# v110.net
KiCad netlist of a schematic drawn in EAGLE
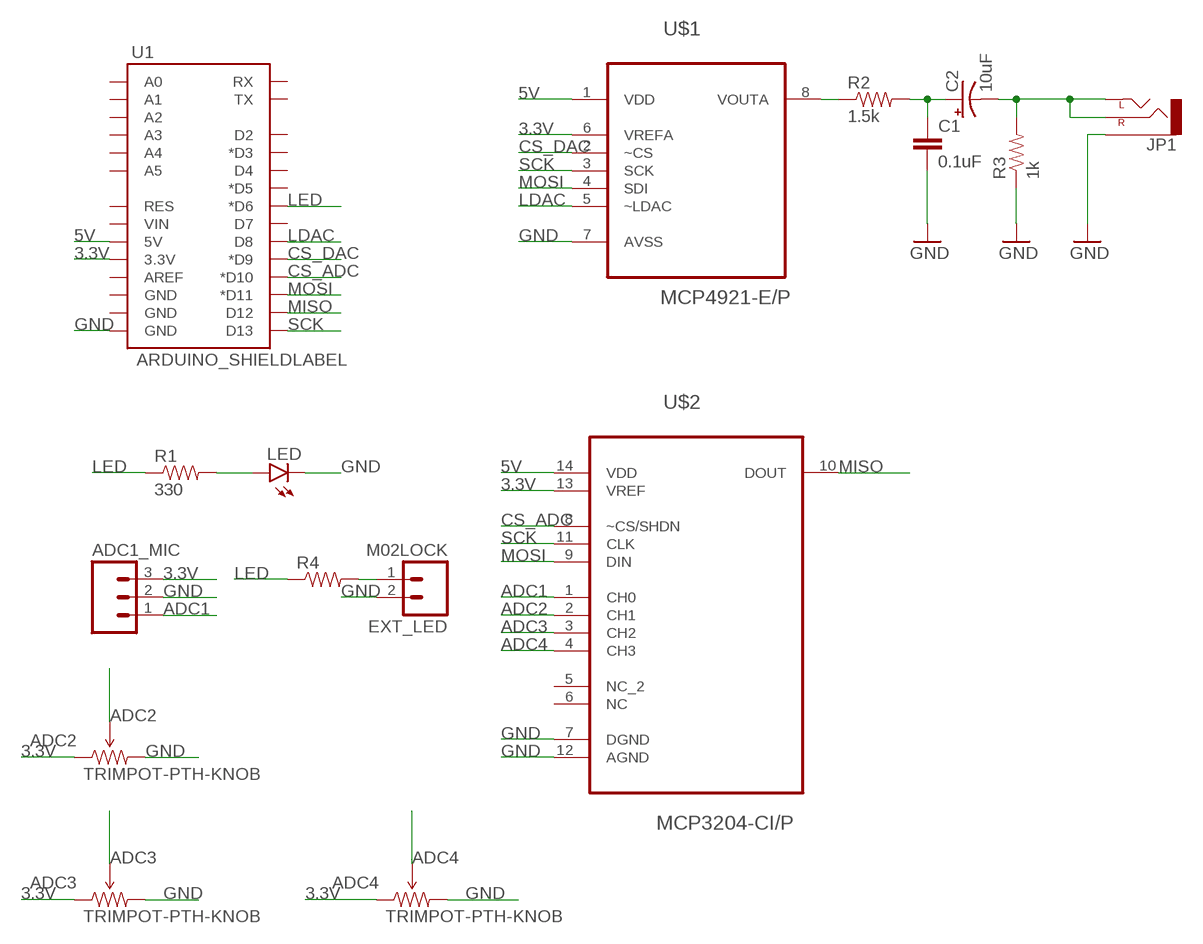
[diagram p0: schematic, sheet 1]

(export (version "E")
  (design (tool "Eeschema 10.0.6"))
  (components
    (comp (ref "ADC1_MIC")
      (value "M03LOCK")
      (footprint "eagle-import:1X03_LOCK")
      (libsource (lib "eagle-import") (part "M03LOCK"))
    )
    (comp (ref "ADC2")
      (value "TRIMPOT-PTH-KNOB")
      (footprint "eagle-import:3386U")
      (libsource (lib "eagle-import") (part "TRIMPOT-PTH-KNOB"))
    )
    (comp (ref "ADC3")
      (value "TRIMPOT-PTH-KNOB")
      (footprint "eagle-import:3386U")
      (libsource (lib "eagle-import") (part "TRIMPOT-PTH-KNOB"))
    )
    (comp (ref "ADC4")
      (value "TRIMPOT-PTH-KNOB")
      (footprint "eagle-import:3386U")
      (libsource (lib "eagle-import") (part "TRIMPOT-PTH-KNOB"))
    )
    (comp (ref "C1")
      (value "0.1uF")
      (footprint "eagle-import:CAP-PTH-5MM")
      (libsource (lib "eagle-import") (part "CAPPTH1"))
    )
    (comp (ref "C2")
      (value "10uF")
      (footprint "eagle-import:CPOL-RADIAL-10UF-25V")
      (libsource (lib "eagle-import") (part "CAP_POLPTH2"))
    )
    (comp (ref "EXT_LED")
      (value "M02LOCK")
      (footprint "eagle-import:1X02_LOCK")
      (libsource (lib "eagle-import") (part "M02LOCK"))
    )
    (comp (ref "JP1")
      (value "AUDIO-JACKPTH")
      (footprint "eagle-import:AUDIO-JACK")
      (libsource (lib "eagle-import") (part "AUDIO-JACKPTH"))
    )
    (comp (ref "LED")
      (value "LED5MM")
      (footprint "eagle-import:LED5MM")
      (libsource (lib "eagle-import") (part "LED5MM"))
    )
    (comp (ref "R1")
      (value "330")
      (footprint "eagle-import:AXIAL-0.3")
      (libsource (lib "eagle-import") (part "1KOHM-1/4W-5%(PTH)"))
    )
    (comp (ref "R2")
      (value "1.5k")
      (footprint "eagle-import:AXIAL-0.3")
      (libsource (lib "eagle-import") (part "1KOHM-1/4W-5%(PTH)"))
    )
    (comp (ref "R3")
      (value "1k")
      (footprint "eagle-import:AXIAL-0.3")
      (libsource (lib "eagle-import") (part "1KOHM-1/4W-5%(PTH)"))
    )
    (comp (ref "R4")
      (value "1KOHM-1/4W-5%(PTH)")
      (footprint "eagle-import:AXIAL-0.3")
      (libsource (lib "eagle-import") (part "1KOHM-1/4W-5%(PTH)"))
    )
    (comp (ref "U$1")
      (value "MCP4921-E/P")
      (footprint "eagle-import:DIP254P762X432-8")
      (libsource (lib "eagle-import") (part "MCP4921-E/P"))
    )
    (comp (ref "U$2")
      (value "MCP3204-CI/P")
      (footprint "eagle-import:DIP254P762X432-14")
      (libsource (lib "eagle-import") (part "MCP3204-CI/P"))
    )
    (comp (ref "U1")
      (value "ARDUINO_SHIELDLABEL")
      (footprint "eagle-import:DUEMILANOVE_SHIELD")
      (libsource (lib "eagle-import") (part "ARDUINO_SHIELDLABEL"))
    )
  )
  (nets
    (net (code "1") (name "/3.3V") (class "Default")
      (node (ref "ADC1_MIC") (pin "3") (pinfunction "3_3") (pintype "passive"))
      (node (ref "ADC2") (pin "1") (pinfunction "CCW_1") (pintype "passive"))
      (node (ref "ADC3") (pin "1") (pinfunction "CCW_1") (pintype "passive"))
      (node (ref "ADC4") (pin "1") (pinfunction "CCW_1") (pintype "passive"))
      (node (ref "U$1") (pin "6") (pinfunction "VREFA_6") (pintype "input"))
      (node (ref "U$2") (pin "13") (pinfunction "VREF_13") (pintype "power_in"))
      (node (ref "U1") (pin "3.3V") (pinfunction "3.3V_3.3V") (pintype "bidirectional"))
    )
    (net (code "2") (name "/5V") (class "Default")
      (node (ref "U$1") (pin "1") (pinfunction "VDD_1") (pintype "power_in"))
      (node (ref "U$2") (pin "14") (pinfunction "VDD_14") (pintype "power_in"))
      (node (ref "U1") (pin "5V") (pinfunction "5V_5V") (pintype "bidirectional"))
    )
    (net (code "3") (name "/ADC1") (class "Default")
      (node (ref "ADC1_MIC") (pin "1") (pinfunction "1_1") (pintype "passive"))
      (node (ref "U$2") (pin "1") (pinfunction "CH0_1") (pintype "input"))
    )
    (net (code "4") (name "/ADC2") (class "Default")
      (node (ref "ADC2") (pin "2") (pinfunction "WIPER_2") (pintype "passive"))
      (node (ref "U$2") (pin "2") (pinfunction "CH1_2") (pintype "input"))
    )
    (net (code "5") (name "/ADC3") (class "Default")
      (node (ref "ADC3") (pin "2") (pinfunction "WIPER_2") (pintype "passive"))
      (node (ref "U$2") (pin "3") (pinfunction "CH2_3") (pintype "input"))
    )
    (net (code "6") (name "/ADC4") (class "Default")
      (node (ref "ADC4") (pin "2") (pinfunction "WIPER_2") (pintype "passive"))
      (node (ref "U$2") (pin "4") (pinfunction "CH3_4") (pintype "input"))
    )
    (net (code "7") (name "/CS_ADC") (class "Default")
      (node (ref "U$2") (pin "8") (pinfunction "~{CS/SHDN}_8") (pintype "input"))
      (node (ref "U1") (pin "D10") (pinfunction "*D10_D10") (pintype "bidirectional"))
    )
    (net (code "8") (name "/CS_DAC") (class "Default")
      (node (ref "U$1") (pin "2") (pinfunction "~{CS}_2") (pintype "input"))
      (node (ref "U1") (pin "D9") (pinfunction "*D9_D9") (pintype "bidirectional"))
    )
    (net (code "9") (name "/LDAC") (class "Default")
      (node (ref "U$1") (pin "5") (pinfunction "~{LDAC}_5") (pintype "input"))
      (node (ref "U1") (pin "D8") (pinfunction "D8_D8") (pintype "bidirectional"))
    )
    (net (code "10") (name "/LED") (class "Default")
      (node (ref "R1") (pin "P$1") (pinfunction "1_P$1") (pintype "passive"))
      (node (ref "R4") (pin "P$1") (pinfunction "1_P$1") (pintype "passive"))
      (node (ref "U1") (pin "D6") (pinfunction "*D6_D6") (pintype "bidirectional"))
    )
    (net (code "11") (name "/MISO") (class "Default")
      (node (ref "U$2") (pin "10") (pinfunction "DOUT_10") (pintype "output"))
      (node (ref "U1") (pin "D12") (pinfunction "D12_D12") (pintype "bidirectional"))
    )
    (net (code "12") (name "/MOSI") (class "Default")
      (node (ref "U$1") (pin "4") (pinfunction "SDI_4") (pintype "input"))
      (node (ref "U$2") (pin "9") (pinfunction "DIN_9") (pintype "input"))
      (node (ref "U1") (pin "D11") (pinfunction "*D11_D11") (pintype "bidirectional"))
    )
    (net (code "13") (name "/SCK") (class "Default")
      (node (ref "U$1") (pin "3") (pinfunction "SCK_3") (pintype "input"))
      (node (ref "U$2") (pin "11") (pinfunction "CLK_11") (pintype "input"))
      (node (ref "U1") (pin "D13") (pinfunction "D13_D13") (pintype "bidirectional"))
    )
    (net (code "14") (name "GND") (class "Default")
      (node (ref "ADC1_MIC") (pin "2") (pinfunction "2_2") (pintype "passive"))
      (node (ref "ADC2") (pin "3") (pinfunction "CW_3") (pintype "passive"))
      (node (ref "ADC3") (pin "3") (pinfunction "CW_3") (pintype "passive"))
      (node (ref "ADC4") (pin "3") (pinfunction "CW_3") (pintype "passive"))
      (node (ref "C1") (pin "2") (pinfunction "2_2") (pintype "passive"))
      (node (ref "EXT_LED") (pin "2") (pinfunction "2_2") (pintype "passive"))
      (node (ref "JP1") (pin "SLEEVE") (pinfunction "SLEEVE_SLEEVE") (pintype "bidirectional"))
      (node (ref "LED") (pin "K") (pinfunction "C_K") (pintype "passive"))
      (node (ref "R3") (pin "P$1") (pinfunction "1_P$1") (pintype "passive"))
      (node (ref "U$1") (pin "7") (pinfunction "AVSS_7") (pintype "passive"))
      (node (ref "U$2") (pin "12") (pinfunction "AGND_12") (pintype "passive"))
      (node (ref "U$2") (pin "7") (pinfunction "DGND_7") (pintype "passive"))
      (node (ref "U1") (pin "GND@0") (pinfunction "GND_GND@0") (pintype "bidirectional"))
    )
    (net (code "15") (name "Net-(C2-+)") (class "Default")
      (node (ref "C1") (pin "1") (pinfunction "1_1") (pintype "passive"))
      (node (ref "C2") (pin "1") (pinfunction "+_1") (pintype "passive"))
      (node (ref "R2") (pin "P$2") (pinfunction "2_P$2") (pintype "passive"))
    )
    (net (code "16") (name "Net-(C2--)") (class "Default")
      (node (ref "C2") (pin "2") (pinfunction "-_2") (pintype "passive"))
      (node (ref "JP1") (pin "RING") (pinfunction "RIGHT_RING") (pintype "bidirectional"))
      (node (ref "JP1") (pin "TIP") (pinfunction "LEFT_TIP") (pintype "bidirectional"))
      (node (ref "R3") (pin "P$2") (pinfunction "2_P$2") (pintype "passive"))
    )
    (net (code "17") (name "Net-(R1-2)") (class "Default")
      (node (ref "LED") (pin "A") (pinfunction "A_A") (pintype "passive"))
      (node (ref "R1") (pin "P$2") (pinfunction "2_P$2") (pintype "passive"))
    )
    (net (code "18") (name "Net-(R2-1)") (class "Default")
      (node (ref "R2") (pin "P$1") (pinfunction "1_P$1") (pintype "passive"))
      (node (ref "U$1") (pin "8") (pinfunction "VOUTA_8") (pintype "output"))
    )
    (net (code "19") (name "Net-(R4-2)") (class "Default")
      (node (ref "EXT_LED") (pin "1") (pinfunction "1_1") (pintype "passive"))
      (node (ref "R4") (pin "P$2") (pinfunction "2_P$2") (pintype "passive"))
    )
    (net (code "20") (name "unconnected-(U$2-NC-Pad6)") (class "Default")
      (node (ref "U$2") (pin "6") (pinfunction "NC_6") (pintype "no_connect"))
    )
    (net (code "21") (name "unconnected-(U$2-NC_2-Pad5)") (class "Default")
      (node (ref "U$2") (pin "5") (pinfunction "NC_2_5") (pintype "no_connect"))
    )
    (net (code "22") (name "unconnected-(U1-*D3-PadD3)") (class "Default")
      (node (ref "U1") (pin "D3") (pinfunction "*D3_D3") (pintype "bidirectional"))
    )
    (net (code "23") (name "unconnected-(U1-*D5-PadD5)") (class "Default")
      (node (ref "U1") (pin "D5") (pinfunction "*D5_D5") (pintype "bidirectional"))
    )
    (net (code "24") (name "unconnected-(U1-GND-PadGND@1)") (class "Default")
      (node (ref "U1") (pin "GND@1") (pinfunction "GND_GND@1") (pintype "bidirectional"))
    )
    (net (code "25") (name "unconnected-(U1-GND-PadGND@2)") (class "Default")
      (node (ref "U1") (pin "GND@2") (pinfunction "GND_GND@2") (pintype "bidirectional"))
    )
    (net (code "26") (name "unconnected-(U1-PadA0)") (class "Default")
      (node (ref "U1") (pin "A0") (pinfunction "A0_A0") (pintype "bidirectional"))
    )
    (net (code "27") (name "unconnected-(U1-PadA1)") (class "Default")
      (node (ref "U1") (pin "A1") (pinfunction "A1_A1") (pintype "bidirectional"))
    )
    (net (code "28") (name "unconnected-(U1-PadA2)") (class "Default")
      (node (ref "U1") (pin "A2") (pinfunction "A2_A2") (pintype "bidirectional"))
    )
    (net (code "29") (name "unconnected-(U1-PadA3)") (class "Default")
      (node (ref "U1") (pin "A3") (pinfunction "A3_A3") (pintype "bidirectional"))
    )
    (net (code "30") (name "unconnected-(U1-PadA4)") (class "Default")
      (node (ref "U1") (pin "A4") (pinfunction "A4_A4") (pintype "bidirectional"))
    )
    (net (code "31") (name "unconnected-(U1-PadA5)") (class "Default")
      (node (ref "U1") (pin "A5") (pinfunction "A5_A5") (pintype "bidirectional"))
    )
    (net (code "32") (name "unconnected-(U1-PadAREF)") (class "Default")
      (node (ref "U1") (pin "AREF") (pinfunction "AREF_AREF") (pintype "bidirectional"))
    )
    (net (code "33") (name "unconnected-(U1-PadD2)") (class "Default")
      (node (ref "U1") (pin "D2") (pinfunction "D2_D2") (pintype "bidirectional"))
    )
    (net (code "34") (name "unconnected-(U1-PadD4)") (class "Default")
      (node (ref "U1") (pin "D4") (pinfunction "D4_D4") (pintype "bidirectional"))
    )
    (net (code "35") (name "unconnected-(U1-PadD7)") (class "Default")
      (node (ref "U1") (pin "D7") (pinfunction "D7_D7") (pintype "bidirectional"))
    )
    (net (code "36") (name "unconnected-(U1-PadRES)") (class "Default")
      (node (ref "U1") (pin "RES") (pinfunction "RES_RES") (pintype "bidirectional"))
    )
    (net (code "37") (name "unconnected-(U1-PadRX)") (class "Default")
      (node (ref "U1") (pin "RX") (pinfunction "RX_RX") (pintype "bidirectional"))
    )
    (net (code "38") (name "unconnected-(U1-PadTX)") (class "Default")
      (node (ref "U1") (pin "TX") (pinfunction "TX_TX") (pintype "bidirectional"))
    )
    (net (code "39") (name "unconnected-(U1-PadVIN)") (class "Default")
      (node (ref "U1") (pin "VIN") (pinfunction "VIN_VIN") (pintype "bidirectional"))
    )
  )
)
